# freezer-monitor.net
KiCad netlist of a schematic drawn in EAGLE
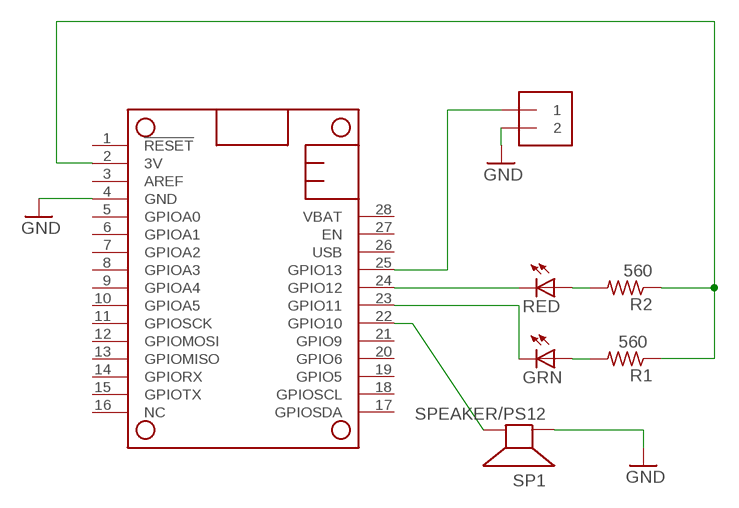
[diagram p0: schematic, sheet 1]

(export (version "E")
  (design (tool "Eeschema 10.0.6"))
  (components
    (comp (ref "GRN")
      (value "LED10MM")
      (footprint "eagle-import:LED10MM")
      (libsource (lib "eagle-import") (part "LED10MM"))
    )
    (comp (ref "J1")
      (value "1X2-3.5MM")
      (footprint "eagle-import:1X2-3.5MM")
      (libsource (lib "eagle-import") (part "1X2-3.5MM"))
    )
    (comp (ref "MS1")
      (value "FEATHERWING")
      (footprint "eagle-import:FEATHERWING")
      (libsource (lib "eagle-import") (part "FEATHERWING"))
    )
    (comp (ref "R1")
      (value "560")
      (footprint "eagle-import:0207_10")
      (libsource (lib "eagle-import") (part "R-US_0207/10"))
    )
    (comp (ref "R2")
      (value "560")
      (footprint "eagle-import:0207_10")
      (libsource (lib "eagle-import") (part "R-US_0207/10"))
    )
    (comp (ref "RED")
      (value "LED10MM")
      (footprint "eagle-import:LED10MM")
      (libsource (lib "eagle-import") (part "LED10MM"))
    )
    (comp (ref "SP1")
      (value "SPEAKER/PS12")
      (footprint "eagle-import:PS12")
      (libsource (lib "eagle-import") (part "SPEAKER/PS12"))
    )
  )
  (nets
    (net (code "1") (name "/USB") (class "Default")
      (node (ref "MS1") (pin "26") (pinfunction "USB_26") (pintype "power_in"))
    )
    (net (code "2") (name "/VBAT") (class "Default")
      (node (ref "MS1") (pin "28") (pinfunction "VBAT_28") (pintype "power_in"))
    )
    (net (code "3") (name "GND") (class "Default")
      (node (ref "J1") (pin "2") (pinfunction "2_2") (pintype "passive"))
      (node (ref "MS1") (pin "4") (pinfunction "GND_4") (pintype "power_in"))
      (node (ref "SP1") (pin "P$1") (pinfunction "+_P$1") (pintype "passive"))
    )
    (net (code "4") (name "Net-(GRN-C)") (class "Default")
      (node (ref "GRN") (pin "K") (pinfunction "C_K") (pintype "passive"))
      (node (ref "MS1") (pin "23") (pinfunction "GPIO11_23") (pintype "bidirectional"))
    )
    (net (code "5") (name "Net-(GRN-PadA)") (class "Default")
      (node (ref "GRN") (pin "A") (pinfunction "A_A") (pintype "passive"))
      (node (ref "R1") (pin "2") (pinfunction "2_2") (pintype "passive"))
    )
    (net (code "6") (name "Net-(MS1-3V)") (class "Default")
      (node (ref "MS1") (pin "2") (pinfunction "3V_2") (pintype "power_in"))
      (node (ref "R1") (pin "1") (pinfunction "1_1") (pintype "passive"))
      (node (ref "R2") (pin "1") (pinfunction "1_1") (pintype "passive"))
    )
    (net (code "7") (name "Net-(MS1-GPIO10)") (class "Default")
      (node (ref "MS1") (pin "22") (pinfunction "GPIO10_22") (pintype "bidirectional"))
      (node (ref "SP1") (pin "P$2") (pinfunction "-_P$2") (pintype "passive"))
    )
    (net (code "8") (name "Net-(MS1-GPIO12)") (class "Default")
      (node (ref "MS1") (pin "24") (pinfunction "GPIO12_24") (pintype "bidirectional"))
      (node (ref "RED") (pin "K") (pinfunction "C_K") (pintype "passive"))
    )
    (net (code "9") (name "Net-(MS1-GPIO13)") (class "Default")
      (node (ref "J1") (pin "1") (pinfunction "1_1") (pintype "passive"))
      (node (ref "MS1") (pin "25") (pinfunction "GPIO13_25") (pintype "bidirectional"))
    )
    (net (code "10") (name "Net-(R2-Pad2)") (class "Default")
      (node (ref "R2") (pin "2") (pinfunction "2_2") (pintype "passive"))
      (node (ref "RED") (pin "A") (pinfunction "A_A") (pintype "passive"))
    )
    (net (code "11") (name "unconnected-(MS1-AREF-Pad3)") (class "Default")
      (node (ref "MS1") (pin "3") (pinfunction "AREF_3") (pintype "passive"))
    )
    (net (code "12") (name "unconnected-(MS1-EN-Pad27)") (class "Default")
      (node (ref "MS1") (pin "27") (pinfunction "EN_27") (pintype "passive"))
    )
    (net (code "13") (name "unconnected-(MS1-GPIO5-Pad19)") (class "Default")
      (node (ref "MS1") (pin "19") (pinfunction "GPIO5_19") (pintype "bidirectional"))
    )
    (net (code "14") (name "unconnected-(MS1-GPIO6-Pad20)") (class "Default")
      (node (ref "MS1") (pin "20") (pinfunction "GPIO6_20") (pintype "bidirectional"))
    )
    (net (code "15") (name "unconnected-(MS1-GPIO9-Pad21)") (class "Default")
      (node (ref "MS1") (pin "21") (pinfunction "GPIO9_21") (pintype "bidirectional"))
    )
    (net (code "16") (name "unconnected-(MS1-GPIOA0-Pad5)") (class "Default")
      (node (ref "MS1") (pin "5") (pinfunction "GPIOA0_5") (pintype "bidirectional"))
    )
    (net (code "17") (name "unconnected-(MS1-GPIOA1-Pad6)") (class "Default")
      (node (ref "MS1") (pin "6") (pinfunction "GPIOA1_6") (pintype "bidirectional"))
    )
    (net (code "18") (name "unconnected-(MS1-GPIOA2-Pad7)") (class "Default")
      (node (ref "MS1") (pin "7") (pinfunction "GPIOA2_7") (pintype "bidirectional"))
    )
    (net (code "19") (name "unconnected-(MS1-GPIOA3-Pad8)") (class "Default")
      (node (ref "MS1") (pin "8") (pinfunction "GPIOA3_8") (pintype "bidirectional"))
    )
    (net (code "20") (name "unconnected-(MS1-GPIOA4-Pad9)") (class "Default")
      (node (ref "MS1") (pin "9") (pinfunction "GPIOA4_9") (pintype "bidirectional"))
    )
    (net (code "21") (name "unconnected-(MS1-GPIOA5-Pad10)") (class "Default")
      (node (ref "MS1") (pin "10") (pinfunction "GPIOA5_10") (pintype "bidirectional"))
    )
    (net (code "22") (name "unconnected-(MS1-GPIOMISO-Pad13)") (class "Default")
      (node (ref "MS1") (pin "13") (pinfunction "GPIOMISO_13") (pintype "bidirectional"))
    )
    (net (code "23") (name "unconnected-(MS1-GPIOMOSI-Pad12)") (class "Default")
      (node (ref "MS1") (pin "12") (pinfunction "GPIOMOSI_12") (pintype "bidirectional"))
    )
    (net (code "24") (name "unconnected-(MS1-GPIORX-Pad14)") (class "Default")
      (node (ref "MS1") (pin "14") (pinfunction "GPIORX_14") (pintype "bidirectional"))
    )
    (net (code "25") (name "unconnected-(MS1-GPIOSCK-Pad11)") (class "Default")
      (node (ref "MS1") (pin "11") (pinfunction "GPIOSCK_11") (pintype "bidirectional"))
    )
    (net (code "26") (name "unconnected-(MS1-GPIOSCL-Pad18)") (class "Default")
      (node (ref "MS1") (pin "18") (pinfunction "GPIOSCL_18") (pintype "bidirectional"))
    )
    (net (code "27") (name "unconnected-(MS1-GPIOSDA-Pad17)") (class "Default")
      (node (ref "MS1") (pin "17") (pinfunction "GPIOSDA_17") (pintype "bidirectional"))
    )
    (net (code "28") (name "unconnected-(MS1-GPIOTX-Pad15)") (class "Default")
      (node (ref "MS1") (pin "15") (pinfunction "GPIOTX_15") (pintype "bidirectional"))
    )
    (net (code "29") (name "unconnected-(MS1-NC-Pad16)") (class "Default")
      (node (ref "MS1") (pin "16") (pinfunction "NC_16") (pintype "passive"))
    )
    (net (code "30") (name "unconnected-(MS1-~{RESET}-Pad1)") (class "Default")
      (node (ref "MS1") (pin "1") (pinfunction "~{RESET}_1") (pintype "input"))
    )
  )
)
